# Banks_9_10.net
KiCad netlist of a schematic drawn in Altium Designer
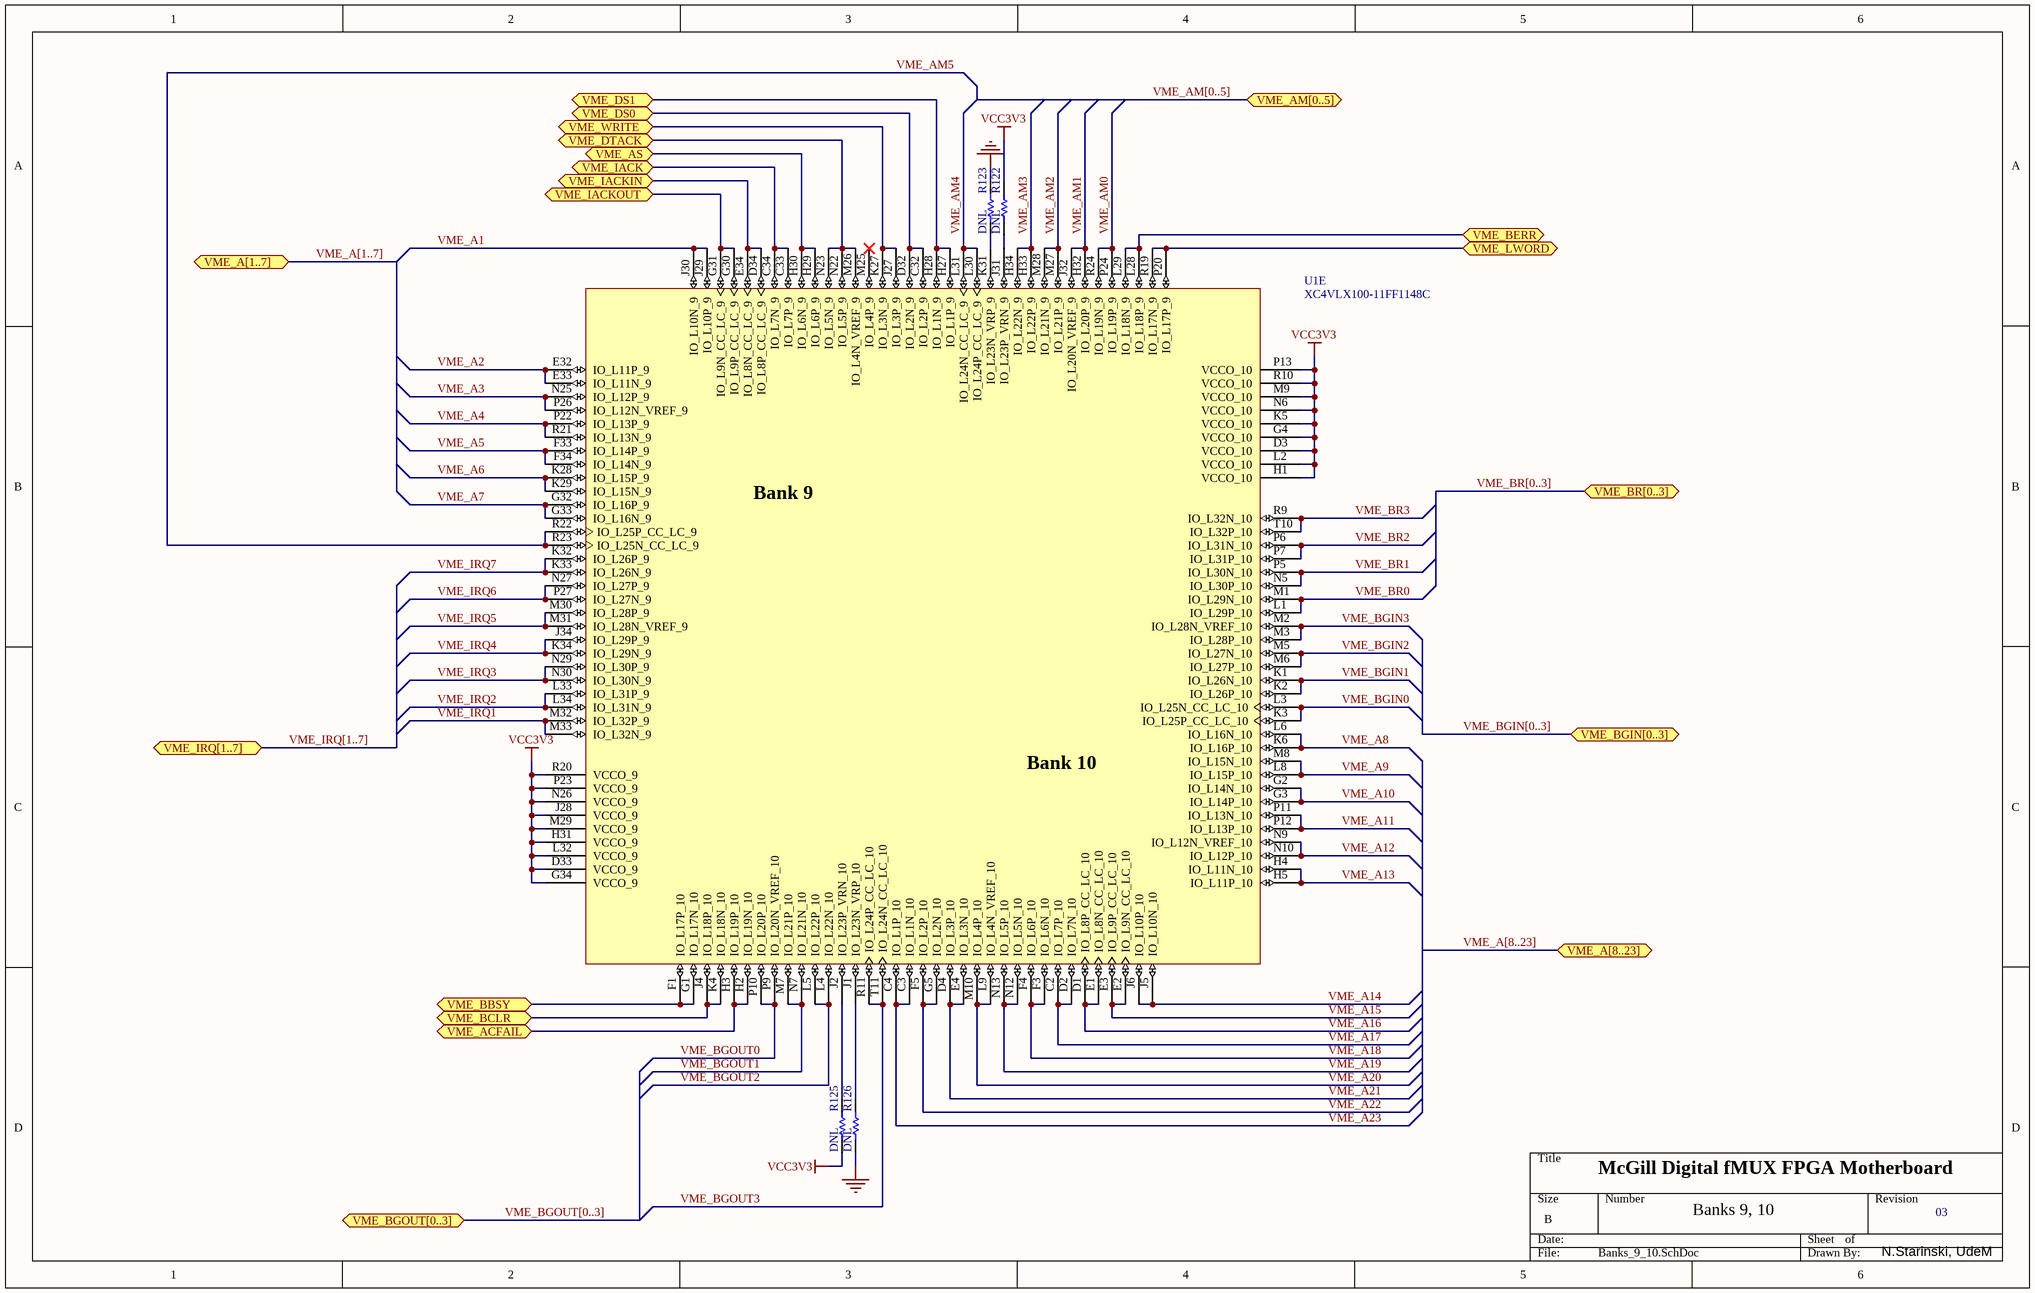
[diagram p0: Banks_9_10.SchDoc]

(export (version "E")
  (design (tool "Eeschema 10.0.6"))
  (components
    (comp (ref "R122")
      (value "DNL")
      (footprint "CR1608-0603")
      (description "Semiconductor Resistor")
      (fields (field (name "PUBLISHER") "Altium Limited"))
      (libsource (lib "Miscellaneous Devices") (part "Res Semi"))
    )
    (comp (ref "R123")
      (value "DNL")
      (footprint "CR1608-0603")
      (description "Semiconductor Resistor")
      (fields (field (name "PUBLISHER") "Altium Limited"))
      (libsource (lib "Miscellaneous Devices") (part "Res Semi"))
    )
    (comp (ref "R125")
      (value "DNL")
      (footprint "CR1608-0603")
      (description "Semiconductor Resistor")
      (fields (field (name "PUBLISHER") "Altium Limited"))
      (libsource (lib "Miscellaneous Devices") (part "Res Semi"))
    )
    (comp (ref "R126")
      (value "DNL")
      (footprint "CR1608-0603")
      (description "Semiconductor Resistor")
      (fields (field (name "PUBLISHER") "Altium Limited"))
      (libsource (lib "Miscellaneous Devices") (part "Res Semi"))
    )
    (comp (ref "U1")
      (value "XC4VLX100-11FF1148C")
      (footprint "FF1148")
      (description "Xilinx Virtex-4 LX Platform FPGA, 1148-Ball FFBGA, Speed Grade 11, 768 User I/Os, Commercial Grade")
      (fields (field (name "PUBLISHER") "Altium Limited"))
      (libsource (lib "Xilinx Virtex-4") (part "XC4VLX100-11FF1148C"))
    )
  )
  (nets
    (net (code "1") (name "/VME_A1") (class "Default")
      (node (ref "U1") (pin "J29") (pinfunction "IO_L10P_9_J29") (pintype "bidirectional"))
      (node (ref "U1") (pin "J30") (pinfunction "IO_L10N_9_J30") (pintype "bidirectional"))
    )
    (net (code "2") (name "/VME_A2") (class "Default")
      (node (ref "U1") (pin "E32") (pinfunction "IO_L11P_9_E32") (pintype "bidirectional"))
      (node (ref "U1") (pin "E33") (pinfunction "IO_L11N_9_E33") (pintype "bidirectional"))
    )
    (net (code "3") (name "/VME_A3") (class "Default")
      (node (ref "U1") (pin "N25") (pinfunction "IO_L12P_9_N25") (pintype "bidirectional"))
      (node (ref "U1") (pin "P26") (pinfunction "IO_L12N_VREF_9_P26") (pintype "bidirectional"))
    )
    (net (code "4") (name "/VME_A4") (class "Default")
      (node (ref "U1") (pin "P22") (pinfunction "IO_L13P_9_P22") (pintype "bidirectional"))
      (node (ref "U1") (pin "R21") (pinfunction "IO_L13N_9_R21") (pintype "bidirectional"))
    )
    (net (code "5") (name "/VME_A5") (class "Default")
      (node (ref "U1") (pin "F33") (pinfunction "IO_L14P_9_F33") (pintype "bidirectional"))
      (node (ref "U1") (pin "F34") (pinfunction "IO_L14N_9_F34") (pintype "bidirectional"))
    )
    (net (code "6") (name "/VME_A6") (class "Default")
      (node (ref "U1") (pin "K28") (pinfunction "IO_L15P_9_K28") (pintype "bidirectional"))
      (node (ref "U1") (pin "K29") (pinfunction "IO_L15N_9_K29") (pintype "bidirectional"))
    )
    (net (code "7") (name "/VME_A7") (class "Default")
      (node (ref "U1") (pin "G32") (pinfunction "IO_L16P_9_G32") (pintype "bidirectional"))
      (node (ref "U1") (pin "G33") (pinfunction "IO_L16N_9_G33") (pintype "bidirectional"))
    )
    (net (code "8") (name "/VME_A8") (class "Default")
      (node (ref "U1") (pin "K6") (pinfunction "IO_L16P_10_K6") (pintype "bidirectional"))
      (node (ref "U1") (pin "L6") (pinfunction "IO_L16N_10_L6") (pintype "bidirectional"))
    )
    (net (code "9") (name "/VME_A9") (class "Default")
      (node (ref "U1") (pin "L8") (pinfunction "IO_L15P_10_L8") (pintype "bidirectional"))
      (node (ref "U1") (pin "M8") (pinfunction "IO_L15N_10_M8") (pintype "bidirectional"))
    )
    (net (code "10") (name "/VME_A10") (class "Default")
      (node (ref "U1") (pin "G2") (pinfunction "IO_L14N_10_G2") (pintype "bidirectional"))
      (node (ref "U1") (pin "G3") (pinfunction "IO_L14P_10_G3") (pintype "bidirectional"))
    )
    (net (code "11") (name "/VME_A11") (class "Default")
      (node (ref "U1") (pin "P11") (pinfunction "IO_L13N_10_P11") (pintype "bidirectional"))
      (node (ref "U1") (pin "P12") (pinfunction "IO_L13P_10_P12") (pintype "bidirectional"))
    )
    (net (code "12") (name "/VME_A12") (class "Default")
      (node (ref "U1") (pin "N10") (pinfunction "IO_L12P_10_N10") (pintype "bidirectional"))
      (node (ref "U1") (pin "N9") (pinfunction "IO_L12N_VREF_10_N9") (pintype "bidirectional"))
    )
    (net (code "13") (name "/VME_A13") (class "Default")
      (node (ref "U1") (pin "H4") (pinfunction "IO_L11N_10_H4") (pintype "bidirectional"))
      (node (ref "U1") (pin "H5") (pinfunction "IO_L11P_10_H5") (pintype "bidirectional"))
    )
    (net (code "14") (name "/VME_A14") (class "Default")
      (node (ref "U1") (pin "J5") (pinfunction "IO_L10N_10_J5") (pintype "bidirectional"))
      (node (ref "U1") (pin "J6") (pinfunction "IO_L10P_10_J6") (pintype "bidirectional"))
    )
    (net (code "15") (name "/VME_A15") (class "Default")
      (node (ref "U1") (pin "E2") (pinfunction "IO_L9N_CC_LC_10_E2") (pintype "bidirectional"))
      (node (ref "U1") (pin "E3") (pinfunction "IO_L9P_CC_LC_10_E3") (pintype "bidirectional"))
    )
    (net (code "16") (name "/VME_A16") (class "Default")
      (node (ref "U1") (pin "D1") (pinfunction "IO_L8P_CC_LC_10_D1") (pintype "bidirectional"))
      (node (ref "U1") (pin "E1") (pinfunction "IO_L8N_CC_LC_10_E1") (pintype "bidirectional"))
    )
    (net (code "17") (name "/VME_A17") (class "Default")
      (node (ref "U1") (pin "C2") (pinfunction "IO_L7P_10_C2") (pintype "bidirectional"))
      (node (ref "U1") (pin "D2") (pinfunction "IO_L7N_10_D2") (pintype "bidirectional"))
    )
    (net (code "18") (name "/VME_A18") (class "Default")
      (node (ref "U1") (pin "F3") (pinfunction "IO_L6N_10_F3") (pintype "bidirectional"))
      (node (ref "U1") (pin "F4") (pinfunction "IO_L6P_10_F4") (pintype "bidirectional"))
    )
    (net (code "19") (name "/VME_A19") (class "Default")
      (node (ref "U1") (pin "N12") (pinfunction "IO_L5N_10_N12") (pintype "bidirectional"))
      (node (ref "U1") (pin "N13") (pinfunction "IO_L5P_10_N13") (pintype "bidirectional"))
    )
    (net (code "20") (name "/VME_A20") (class "Default")
      (node (ref "U1") (pin "L9") (pinfunction "IO_L4N_VREF_10_L9") (pintype "bidirectional"))
      (node (ref "U1") (pin "M10") (pinfunction "IO_L4P_10_M10") (pintype "bidirectional"))
    )
    (net (code "21") (name "/VME_A21") (class "Default")
      (node (ref "U1") (pin "D4") (pinfunction "IO_L3P_10_D4") (pintype "bidirectional"))
      (node (ref "U1") (pin "E4") (pinfunction "IO_L3N_10_E4") (pintype "bidirectional"))
    )
    (net (code "22") (name "/VME_A22") (class "Default")
      (node (ref "U1") (pin "F5") (pinfunction "IO_L2P_10_F5") (pintype "bidirectional"))
      (node (ref "U1") (pin "G5") (pinfunction "IO_L2N_10_G5") (pintype "bidirectional"))
    )
    (net (code "23") (name "/VME_A23") (class "Default")
      (node (ref "U1") (pin "C3") (pinfunction "IO_L1N_10_C3") (pintype "bidirectional"))
      (node (ref "U1") (pin "C4") (pinfunction "IO_L1P_10_C4") (pintype "bidirectional"))
    )
    (net (code "24") (name "/VME_ACFAIL") (class "Default")
      (node (ref "U1") (pin "H2") (pinfunction "IO_L19N_10_H2") (pintype "bidirectional"))
      (node (ref "U1") (pin "H3") (pinfunction "IO_L19P_10_H3") (pintype "bidirectional"))
    )
    (net (code "25") (name "/VME_AM0") (class "Default")
      (node (ref "U1") (pin "P24") (pinfunction "IO_L19P_9_P24") (pintype "bidirectional"))
      (node (ref "U1") (pin "R24") (pinfunction "IO_L19N_9_R24") (pintype "bidirectional"))
    )
    (net (code "26") (name "/VME_AM1") (class "Default")
      (node (ref "U1") (pin "H32") (pinfunction "IO_L20P_9_H32") (pintype "bidirectional"))
      (node (ref "U1") (pin "J32") (pinfunction "IO_L20N_VREF_9_J32") (pintype "bidirectional"))
    )
    (net (code "27") (name "/VME_AM2") (class "Default")
      (node (ref "U1") (pin "M27") (pinfunction "IO_L21P_9_M27") (pintype "bidirectional"))
      (node (ref "U1") (pin "M28") (pinfunction "IO_L21N_9_M28") (pintype "bidirectional"))
    )
    (net (code "28") (name "/VME_AM3") (class "Default")
      (node (ref "U1") (pin "H33") (pinfunction "IO_L22P_9_H33") (pintype "bidirectional"))
      (node (ref "U1") (pin "H34") (pinfunction "IO_L22N_9_H34") (pintype "bidirectional"))
    )
    (net (code "29") (name "/VME_AM4") (class "Default")
      (node (ref "U1") (pin "L30") (pinfunction "IO_L24P_CC_LC_9_L30") (pintype "bidirectional"))
      (node (ref "U1") (pin "L31") (pinfunction "IO_L24N_CC_LC_9_L31") (pintype "bidirectional"))
    )
    (net (code "30") (name "/VME_AM5") (class "Default")
      (node (ref "U1") (pin "R22") (pinfunction "IO_L25P_CC_LC_9_R22") (pintype "bidirectional"))
      (node (ref "U1") (pin "R23") (pinfunction "IO_L25N_CC_LC_9_R23") (pintype "bidirectional"))
    )
    (net (code "32") (name "/VME_AS") (class "Default")
      (node (ref "U1") (pin "H29") (pinfunction "IO_L6P_9_H29") (pintype "bidirectional"))
      (node (ref "U1") (pin "H30") (pinfunction "IO_L6N_9_H30") (pintype "bidirectional"))
    )
    (net (code "35") (name "/VME_BBSY") (class "Default")
      (node (ref "U1") (pin "F1") (pinfunction "IO_L17P_10_F1") (pintype "bidirectional"))
      (node (ref "U1") (pin "G1") (pinfunction "IO_L17N_10_G1") (pintype "bidirectional"))
    )
    (net (code "36") (name "/VME_BCLR") (class "Default")
      (node (ref "U1") (pin "J4") (pinfunction "IO_L18P_10_J4") (pintype "bidirectional"))
      (node (ref "U1") (pin "K4") (pinfunction "IO_L18N_10_K4") (pintype "bidirectional"))
    )
    (net (code "37") (name "/VME_BERR") (class "Default")
      (node (ref "U1") (pin "L28") (pinfunction "IO_L18P_9_L28") (pintype "bidirectional"))
      (node (ref "U1") (pin "L29") (pinfunction "IO_L18N_9_L29") (pintype "bidirectional"))
    )
    (net (code "38") (name "/VME_BGIN0") (class "Default")
      (node (ref "U1") (pin "K3") (pinfunction "IO_L25P_CC_LC_10_K3") (pintype "bidirectional"))
      (node (ref "U1") (pin "L3") (pinfunction "IO_L25N_CC_LC_10_L3") (pintype "bidirectional"))
    )
    (net (code "39") (name "/VME_BGIN1") (class "Default")
      (node (ref "U1") (pin "K1") (pinfunction "IO_L26N_10_K1") (pintype "bidirectional"))
      (node (ref "U1") (pin "K2") (pinfunction "IO_L26P_10_K2") (pintype "bidirectional"))
    )
    (net (code "40") (name "/VME_BGIN2") (class "Default")
      (node (ref "U1") (pin "M5") (pinfunction "IO_L27N_10_M5") (pintype "bidirectional"))
      (node (ref "U1") (pin "M6") (pinfunction "IO_L27P_10_M6") (pintype "bidirectional"))
    )
    (net (code "41") (name "/VME_BGIN3") (class "Default")
      (node (ref "U1") (pin "M2") (pinfunction "IO_L28N_VREF_10_M2") (pintype "bidirectional"))
      (node (ref "U1") (pin "M3") (pinfunction "IO_L28P_10_M3") (pintype "bidirectional"))
    )
    (net (code "43") (name "/VME_BGOUT0") (class "Default")
      (node (ref "U1") (pin "P10") (pinfunction "IO_L20P_10_P10") (pintype "bidirectional"))
      (node (ref "U1") (pin "P9") (pinfunction "IO_L20N_VREF_10_P9") (pintype "bidirectional"))
    )
    (net (code "44") (name "/VME_BGOUT1") (class "Default")
      (node (ref "U1") (pin "M7") (pinfunction "IO_L21P_10_M7") (pintype "bidirectional"))
      (node (ref "U1") (pin "N7") (pinfunction "IO_L21N_10_N7") (pintype "bidirectional"))
    )
    (net (code "45") (name "/VME_BGOUT2") (class "Default")
      (node (ref "U1") (pin "L4") (pinfunction "IO_L22N_10_L4") (pintype "bidirectional"))
      (node (ref "U1") (pin "L5") (pinfunction "IO_L22P_10_L5") (pintype "bidirectional"))
    )
    (net (code "46") (name "/VME_BGOUT3") (class "Default")
      (node (ref "U1") (pin "R11") (pinfunction "IO_L24P_CC_LC_10_R11") (pintype "bidirectional"))
      (node (ref "U1") (pin "T11") (pinfunction "IO_L24N_CC_LC_10_T11") (pintype "bidirectional"))
    )
    (net (code "48") (name "/VME_BR0") (class "Default")
      (node (ref "U1") (pin "L1") (pinfunction "IO_L29P_10_L1") (pintype "bidirectional"))
      (node (ref "U1") (pin "M1") (pinfunction "IO_L29N_10_M1") (pintype "bidirectional"))
    )
    (net (code "49") (name "/VME_BR1") (class "Default")
      (node (ref "U1") (pin "N5") (pinfunction "IO_L30P_10_N5") (pintype "bidirectional"))
      (node (ref "U1") (pin "P5") (pinfunction "IO_L30N_10_P5") (pintype "bidirectional"))
    )
    (net (code "50") (name "/VME_BR2") (class "Default")
      (node (ref "U1") (pin "P6") (pinfunction "IO_L31N_10_P6") (pintype "bidirectional"))
      (node (ref "U1") (pin "P7") (pinfunction "IO_L31P_10_P7") (pintype "bidirectional"))
    )
    (net (code "51") (name "/VME_BR3") (class "Default")
      (node (ref "U1") (pin "R9") (pinfunction "IO_L32N_10_R9") (pintype "bidirectional"))
      (node (ref "U1") (pin "T10") (pinfunction "IO_L32P_10_T10") (pintype "bidirectional"))
    )
    (net (code "53") (name "/VME_DS0") (class "Default")
      (node (ref "U1") (pin "C32") (pinfunction "IO_L2P_9_C32") (pintype "bidirectional"))
      (node (ref "U1") (pin "D32") (pinfunction "IO_L2N_9_D32") (pintype "bidirectional"))
    )
    (net (code "54") (name "/VME_DS1") (class "Default")
      (node (ref "U1") (pin "H27") (pinfunction "IO_L1P_9_H27") (pintype "bidirectional"))
      (node (ref "U1") (pin "H28") (pinfunction "IO_L1N_9_H28") (pintype "bidirectional"))
    )
    (net (code "55") (name "/VME_DTACK") (class "Default")
      (node (ref "U1") (pin "M26") (pinfunction "IO_L4N_VREF_9_M26") (pintype "bidirectional"))
      (node (ref "U1") (pin "N22") (pinfunction "IO_L5P_9_N22") (pintype "bidirectional"))
      (node (ref "U1") (pin "N23") (pinfunction "IO_L5N_9_N23") (pintype "bidirectional"))
    )
    (net (code "56") (name "/VME_IACK") (class "Default")
      (node (ref "U1") (pin "C33") (pinfunction "IO_L7P_9_C33") (pintype "bidirectional"))
      (node (ref "U1") (pin "C34") (pinfunction "IO_L7N_9_C34") (pintype "bidirectional"))
    )
    (net (code "57") (name "/VME_IACKIN") (class "Default")
      (node (ref "U1") (pin "D34") (pinfunction "IO_L8P_CC_LC_9_D34") (pintype "bidirectional"))
      (node (ref "U1") (pin "E34") (pinfunction "IO_L8N_CC_LC_9_E34") (pintype "bidirectional"))
    )
    (net (code "58") (name "/VME_IACKOUT") (class "Default")
      (node (ref "U1") (pin "G30") (pinfunction "IO_L9P_CC_LC_9_G30") (pintype "bidirectional"))
      (node (ref "U1") (pin "G31") (pinfunction "IO_L9N_CC_LC_9_G31") (pintype "bidirectional"))
    )
    (net (code "59") (name "/VME_IRQ1") (class "Default")
      (node (ref "U1") (pin "M32") (pinfunction "IO_L32P_9_M32") (pintype "bidirectional"))
      (node (ref "U1") (pin "M33") (pinfunction "IO_L32N_9_M33") (pintype "bidirectional"))
    )
    (net (code "60") (name "/VME_IRQ2") (class "Default")
      (node (ref "U1") (pin "L33") (pinfunction "IO_L31P_9_L33") (pintype "bidirectional"))
      (node (ref "U1") (pin "L34") (pinfunction "IO_L31N_9_L34") (pintype "bidirectional"))
    )
    (net (code "61") (name "/VME_IRQ3") (class "Default")
      (node (ref "U1") (pin "N29") (pinfunction "IO_L30P_9_N29") (pintype "bidirectional"))
      (node (ref "U1") (pin "N30") (pinfunction "IO_L30N_9_N30") (pintype "bidirectional"))
    )
    (net (code "62") (name "/VME_IRQ4") (class "Default")
      (node (ref "U1") (pin "J34") (pinfunction "IO_L29P_9_J34") (pintype "bidirectional"))
      (node (ref "U1") (pin "K34") (pinfunction "IO_L29N_9_K34") (pintype "bidirectional"))
    )
    (net (code "63") (name "/VME_IRQ5") (class "Default")
      (node (ref "U1") (pin "M30") (pinfunction "IO_L28P_9_M30") (pintype "bidirectional"))
      (node (ref "U1") (pin "M31") (pinfunction "IO_L28N_VREF_9_M31") (pintype "bidirectional"))
    )
    (net (code "64") (name "/VME_IRQ6") (class "Default")
      (node (ref "U1") (pin "N27") (pinfunction "IO_L27P_9_N27") (pintype "bidirectional"))
      (node (ref "U1") (pin "P27") (pinfunction "IO_L27N_9_P27") (pintype "bidirectional"))
    )
    (net (code "65") (name "/VME_IRQ7") (class "Default")
      (node (ref "U1") (pin "K32") (pinfunction "IO_L26P_9_K32") (pintype "bidirectional"))
      (node (ref "U1") (pin "K33") (pinfunction "IO_L26N_9_K33") (pintype "bidirectional"))
    )
    (net (code "67") (name "/VME_LWORD") (class "Default")
      (node (ref "U1") (pin "P20") (pinfunction "IO_L17P_9_P20") (pintype "bidirectional"))
      (node (ref "U1") (pin "R19") (pinfunction "IO_L17N_9_R19") (pintype "bidirectional"))
    )
    (net (code "68") (name "/VME_WRITE") (class "Default")
      (node (ref "U1") (pin "J27") (pinfunction "IO_L3P_9_J27") (pintype "bidirectional"))
      (node (ref "U1") (pin "K27") (pinfunction "IO_L3N_9_K27") (pintype "bidirectional"))
    )
    (net (code "69") (name "GND") (class "Default")
      (node (ref "R123") (pin "2") (pinfunction "2_2") (pintype "passive"))
      (node (ref "R126") (pin "1") (pinfunction "1_1") (pintype "passive"))
    )
    (net (code "70") (name "Net-(U1E-IO_L23N_VRP_9)") (class "Default")
      (node (ref "R123") (pin "1") (pinfunction "1_1") (pintype "passive"))
      (node (ref "U1") (pin "K31") (pinfunction "IO_L23N_VRP_9_K31") (pintype "bidirectional"))
    )
    (net (code "71") (name "Net-(U1E-IO_L23N_VRP_10)") (class "Default")
      (node (ref "R126") (pin "2") (pinfunction "2_2") (pintype "passive"))
      (node (ref "U1") (pin "J1") (pinfunction "IO_L23N_VRP_10_J1") (pintype "bidirectional"))
    )
    (net (code "72") (name "Net-(U1E-IO_L23P_VRN_9)") (class "Default")
      (node (ref "R122") (pin "1") (pinfunction "1_1") (pintype "passive"))
      (node (ref "U1") (pin "J31") (pinfunction "IO_L23P_VRN_9_J31") (pintype "bidirectional"))
    )
    (net (code "73") (name "Net-(U1E-IO_L23P_VRN_10)") (class "Default")
      (node (ref "R125") (pin "2") (pinfunction "2_2") (pintype "passive"))
      (node (ref "U1") (pin "J2") (pinfunction "IO_L23P_VRN_10_J2") (pintype "bidirectional"))
    )
    (net (code "74") (name "VCC3V3") (class "Default")
      (node (ref "R122") (pin "2") (pinfunction "2_2") (pintype "passive"))
      (node (ref "R125") (pin "1") (pinfunction "1_1") (pintype "passive"))
      (node (ref "U1") (pin "D3") (pinfunction "VCCO_10_D3") (pintype "power_in"))
      (node (ref "U1") (pin "D33") (pinfunction "VCCO_9_D33") (pintype "power_in"))
      (node (ref "U1") (pin "G34") (pinfunction "VCCO_9_G34") (pintype "power_in"))
      (node (ref "U1") (pin "G4") (pinfunction "VCCO_10_G4") (pintype "power_in"))
      (node (ref "U1") (pin "H1") (pinfunction "VCCO_10_H1") (pintype "power_in"))
      (node (ref "U1") (pin "H31") (pinfunction "VCCO_9_H31") (pintype "power_in"))
      (node (ref "U1") (pin "J28") (pinfunction "VCCO_9_J28") (pintype "power_in"))
      (node (ref "U1") (pin "K5") (pinfunction "VCCO_10_K5") (pintype "power_in"))
      (node (ref "U1") (pin "L2") (pinfunction "VCCO_10_L2") (pintype "power_in"))
      (node (ref "U1") (pin "L32") (pinfunction "VCCO_9_L32") (pintype "power_in"))
      (node (ref "U1") (pin "M29") (pinfunction "VCCO_9_M29") (pintype "power_in"))
      (node (ref "U1") (pin "M9") (pinfunction "VCCO_10_M9") (pintype "power_in"))
      (node (ref "U1") (pin "N26") (pinfunction "VCCO_9_N26") (pintype "power_in"))
      (node (ref "U1") (pin "N6") (pinfunction "VCCO_10_N6") (pintype "power_in"))
      (node (ref "U1") (pin "P13") (pinfunction "VCCO_10_P13") (pintype "power_in"))
      (node (ref "U1") (pin "P23") (pinfunction "VCCO_9_P23") (pintype "power_in"))
      (node (ref "U1") (pin "R10") (pinfunction "VCCO_10_R10") (pintype "power_in"))
      (node (ref "U1") (pin "R20") (pinfunction "VCCO_9_R20") (pintype "power_in"))
    )
    (net (code "75") (name "unconnected-(U1E-IO_L4P_9-PadM25)") (class "Default")
      (node (ref "U1") (pin "M25") (pinfunction "IO_L4P_9_M25") (pintype "bidirectional+no_connect"))
    )
  )
)
